# NCS_Wireless_Indicator_leds.net
KiCad netlist of a schematic drawn in Altium Designer
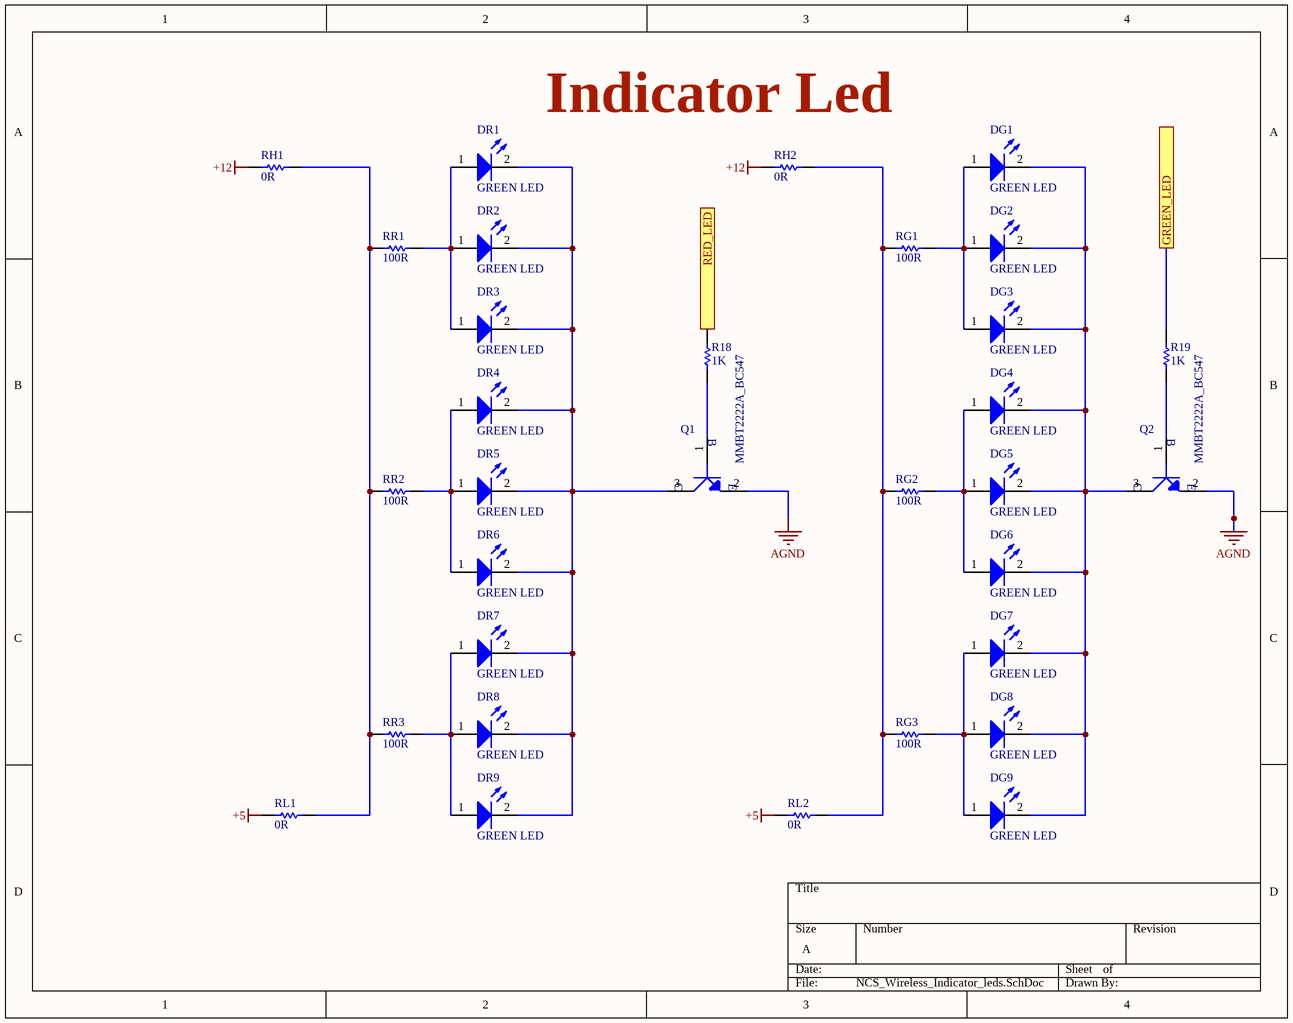
[diagram p0: NCS_Wireless_Indicator_leds.SchDoc]

(export (version "E")
  (design (tool "Eeschema 10.0.6"))
  (components
    (comp (ref "DG1")
      (value "GREEN LED")
      (footprint "LED_1208")
      (description "LED Uni-Color Red 2-Pin Chip 1208(3020Metric) T/R")
      (fields
        (field (name "MANUFACTURER") "QT-Brightek")
        (field (name "MANUFACTURER PART NUMBER") "QBLP653-R")
      )
      (libsource (lib "schlib") (part "QBLP653-R"))
    )
    (comp (ref "DG2")
      (value "GREEN LED")
      (footprint "LED_1208")
      (description "LED Uni-Color Red 2-Pin Chip 1208(3020Metric) T/R")
      (fields
        (field (name "MANUFACTURER") "QT-Brightek")
        (field (name "MANUFACTURER PART NUMBER") "QBLP653-R")
      )
      (libsource (lib "schlib") (part "QBLP653-R"))
    )
    (comp (ref "DG3")
      (value "GREEN LED")
      (footprint "LED_1208")
      (description "LED Uni-Color Red 2-Pin Chip 1208(3020Metric) T/R")
      (fields
        (field (name "MANUFACTURER") "QT-Brightek")
        (field (name "MANUFACTURER PART NUMBER") "QBLP653-R")
      )
      (libsource (lib "schlib") (part "QBLP653-R"))
    )
    (comp (ref "DG4")
      (value "GREEN LED")
      (footprint "LED_1208")
      (description "LED Uni-Color Red 2-Pin Chip 1208(3020Metric) T/R")
      (fields
        (field (name "MANUFACTURER") "QT-Brightek")
        (field (name "MANUFACTURER PART NUMBER") "QBLP653-R")
      )
      (libsource (lib "schlib") (part "QBLP653-R"))
    )
    (comp (ref "DG5")
      (value "GREEN LED")
      (footprint "LED_1208")
      (description "LED Uni-Color Red 2-Pin Chip 1208(3020Metric) T/R")
      (fields
        (field (name "MANUFACTURER") "QT-Brightek")
        (field (name "MANUFACTURER PART NUMBER") "QBLP653-R")
      )
      (libsource (lib "schlib") (part "QBLP653-R"))
    )
    (comp (ref "DG6")
      (value "GREEN LED")
      (footprint "LED_1208")
      (description "LED Uni-Color Red 2-Pin Chip 1208(3020Metric) T/R")
      (fields
        (field (name "MANUFACTURER") "QT-Brightek")
        (field (name "MANUFACTURER PART NUMBER") "QBLP653-R")
      )
      (libsource (lib "schlib") (part "QBLP653-R"))
    )
    (comp (ref "DG7")
      (value "GREEN LED")
      (footprint "LED_1208")
      (description "LED Uni-Color Red 2-Pin Chip 1208(3020Metric) T/R")
      (fields
        (field (name "MANUFACTURER") "QT-Brightek")
        (field (name "MANUFACTURER PART NUMBER") "QBLP653-R")
      )
      (libsource (lib "schlib") (part "QBLP653-R"))
    )
    (comp (ref "DG8")
      (value "GREEN LED")
      (footprint "LED_1208")
      (description "LED Uni-Color Red 2-Pin Chip 1208(3020Metric) T/R")
      (fields
        (field (name "MANUFACTURER") "QT-Brightek")
        (field (name "MANUFACTURER PART NUMBER") "QBLP653-R")
      )
      (libsource (lib "schlib") (part "QBLP653-R"))
    )
    (comp (ref "DG9")
      (value "GREEN LED")
      (footprint "LED_1208")
      (description "LED Uni-Color Red 2-Pin Chip 1208(3020Metric) T/R")
      (fields
        (field (name "MANUFACTURER") "QT-Brightek")
        (field (name "MANUFACTURER PART NUMBER") "QBLP653-R")
      )
      (libsource (lib "schlib") (part "QBLP653-R"))
    )
    (comp (ref "DR1")
      (value "GREEN LED")
      (footprint "LED_1208")
      (description "LED Uni-Color Red 2-Pin Chip 1208(3020Metric) T/R")
      (fields
        (field (name "MANUFACTURER") "QT-Brightek")
        (field (name "MANUFACTURER PART NUMBER") "QBLP653-R")
      )
      (libsource (lib "schlib") (part "QBLP653-R"))
    )
    (comp (ref "DR2")
      (value "GREEN LED")
      (footprint "LED_1208")
      (description "LED Uni-Color Red 2-Pin Chip 1208(3020Metric) T/R")
      (fields
        (field (name "MANUFACTURER") "QT-Brightek")
        (field (name "MANUFACTURER PART NUMBER") "QBLP653-R")
      )
      (libsource (lib "schlib") (part "QBLP653-R"))
    )
    (comp (ref "DR3")
      (value "GREEN LED")
      (footprint "LED_1208")
      (description "LED Uni-Color Red 2-Pin Chip 1208(3020Metric) T/R")
      (fields
        (field (name "MANUFACTURER") "QT-Brightek")
        (field (name "MANUFACTURER PART NUMBER") "QBLP653-R")
      )
      (libsource (lib "schlib") (part "QBLP653-R"))
    )
    (comp (ref "DR4")
      (value "GREEN LED")
      (footprint "LED_1208")
      (description "LED Uni-Color Red 2-Pin Chip 1208(3020Metric) T/R")
      (fields
        (field (name "MANUFACTURER") "QT-Brightek")
        (field (name "MANUFACTURER PART NUMBER") "QBLP653-R")
      )
      (libsource (lib "schlib") (part "QBLP653-R"))
    )
    (comp (ref "DR5")
      (value "GREEN LED")
      (footprint "LED_1208")
      (description "LED Uni-Color Red 2-Pin Chip 1208(3020Metric) T/R")
      (fields
        (field (name "MANUFACTURER") "QT-Brightek")
        (field (name "MANUFACTURER PART NUMBER") "QBLP653-R")
      )
      (libsource (lib "schlib") (part "QBLP653-R"))
    )
    (comp (ref "DR6")
      (value "GREEN LED")
      (footprint "LED_1208")
      (description "LED Uni-Color Red 2-Pin Chip 1208(3020Metric) T/R")
      (fields
        (field (name "MANUFACTURER") "QT-Brightek")
        (field (name "MANUFACTURER PART NUMBER") "QBLP653-R")
      )
      (libsource (lib "schlib") (part "QBLP653-R"))
    )
    (comp (ref "DR7")
      (value "GREEN LED")
      (footprint "LED_1208")
      (description "LED Uni-Color Red 2-Pin Chip 1208(3020Metric) T/R")
      (fields
        (field (name "MANUFACTURER") "QT-Brightek")
        (field (name "MANUFACTURER PART NUMBER") "QBLP653-R")
      )
      (libsource (lib "schlib") (part "QBLP653-R"))
    )
    (comp (ref "DR8")
      (value "GREEN LED")
      (footprint "LED_1208")
      (description "LED Uni-Color Red 2-Pin Chip 1208(3020Metric) T/R")
      (fields
        (field (name "MANUFACTURER") "QT-Brightek")
        (field (name "MANUFACTURER PART NUMBER") "QBLP653-R")
      )
      (libsource (lib "schlib") (part "QBLP653-R"))
    )
    (comp (ref "DR9")
      (value "GREEN LED")
      (footprint "LED_1208")
      (description "LED Uni-Color Red 2-Pin Chip 1208(3020Metric) T/R")
      (fields
        (field (name "MANUFACTURER") "QT-Brightek")
        (field (name "MANUFACTURER PART NUMBER") "QBLP653-R")
      )
      (libsource (lib "schlib") (part "QBLP653-R"))
    )
    (comp (ref "Q1")
      (value "MMBT2222A_BC547")
      (footprint "MMBT2222A_SOT23")
      (description "Trans GP BJT NPN 40V 0.6A 250mW Automotive 3-Pin SOT-23 T/R")
      (fields (field (name "MANUFACTURER") "Infineon") (field (name "MANUFACTURER PART NUMBER") "MMBT2222A"))
      (libsource (lib "BSCU_SMD_lib") (part "MMBT2222A"))
    )
    (comp (ref "Q2")
      (value "MMBT2222A_BC547")
      (footprint "MMBT2222A_SOT23")
      (description "Trans GP BJT NPN 40V 0.6A 250mW Automotive 3-Pin SOT-23 T/R")
      (fields (field (name "MANUFACTURER") "Infineon") (field (name "MANUFACTURER PART NUMBER") "MMBT2222A"))
      (libsource (lib "BSCU_SMD_lib") (part "MMBT2222A"))
    )
    (comp (ref "R18")
      (value "1K")
      (footprint "RC0805FR-7W330RL")
      (description "Res Thick Film 0805 330 Ohm 1% 0.25W(1/4W) ±200ppm/C Pad SMD T/R")
      (fields
        (field (name "MANUFACTURER") "Yageo")
        (field (name "MANUFACTURER PART NUMBER") "RC0805FR-7W330RL")
      )
      (libsource (lib "schlib") (part "RC0805FR-7W330RL"))
    )
    (comp (ref "R19")
      (value "1K")
      (footprint "RC0805FR-7W330RL")
      (description "Res Thick Film 0805 330 Ohm 1% 0.25W(1/4W) ±200ppm/C Pad SMD T/R")
      (fields
        (field (name "MANUFACTURER") "Yageo")
        (field (name "MANUFACTURER PART NUMBER") "RC0805FR-7W330RL")
      )
      (libsource (lib "schlib") (part "RC0805FR-7W330RL"))
    )
    (comp (ref "RG1")
      (value "100R")
      (footprint "RC0805FR-7W330RL")
      (description "Res Thick Film 0805 330 Ohm 1% 0.25W(1/4W) ±200ppm/C Pad SMD T/R")
      (fields
        (field (name "MANUFACTURER") "Yageo")
        (field (name "MANUFACTURER PART NUMBER") "RC0805FR-7W330RL")
      )
      (libsource (lib "schlib") (part "RC0805FR-7W330RL"))
    )
    (comp (ref "RG2")
      (value "100R")
      (footprint "RC0805FR-7W330RL")
      (description "Res Thick Film 0805 330 Ohm 1% 0.25W(1/4W) ±200ppm/C Pad SMD T/R")
      (fields
        (field (name "MANUFACTURER") "Yageo")
        (field (name "MANUFACTURER PART NUMBER") "RC0805FR-7W330RL")
      )
      (libsource (lib "schlib") (part "RC0805FR-7W330RL"))
    )
    (comp (ref "RG3")
      (value "100R")
      (footprint "RC0805FR-7W330RL")
      (description "Res Thick Film 0805 330 Ohm 1% 0.25W(1/4W) ±200ppm/C Pad SMD T/R")
      (fields
        (field (name "MANUFACTURER") "Yageo")
        (field (name "MANUFACTURER PART NUMBER") "RC0805FR-7W330RL")
      )
      (libsource (lib "schlib") (part "RC0805FR-7W330RL"))
    )
    (comp (ref "RH1")
      (value "0R")
      (footprint "RC0805FR-7W330RL")
      (description "Res Thick Film 0805 330 Ohm 1% 0.25W(1/4W) ±200ppm/C Pad SMD T/R")
      (fields
        (field (name "MANUFACTURER") "Yageo")
        (field (name "MANUFACTURER PART NUMBER") "RC0805FR-7W330RL")
      )
      (libsource (lib "schlib") (part "RC0805FR-7W330RL"))
    )
    (comp (ref "RH2")
      (value "0R")
      (footprint "RC0805FR-7W330RL")
      (description "Res Thick Film 0805 330 Ohm 1% 0.25W(1/4W) ±200ppm/C Pad SMD T/R")
      (fields
        (field (name "MANUFACTURER") "Yageo")
        (field (name "MANUFACTURER PART NUMBER") "RC0805FR-7W330RL")
      )
      (libsource (lib "schlib") (part "RC0805FR-7W330RL"))
    )
    (comp (ref "RL1")
      (value "0R")
      (footprint "RC0805FR-7W330RL")
      (description "Res Thick Film 0805 330 Ohm 1% 0.25W(1/4W) ±200ppm/C Pad SMD T/R")
      (fields
        (field (name "MANUFACTURER") "Yageo")
        (field (name "MANUFACTURER PART NUMBER") "RC0805FR-7W330RL")
      )
      (libsource (lib "schlib") (part "RC0805FR-7W330RL"))
    )
    (comp (ref "RL2")
      (value "0R")
      (footprint "RC0805FR-7W330RL")
      (description "Res Thick Film 0805 330 Ohm 1% 0.25W(1/4W) ±200ppm/C Pad SMD T/R")
      (fields
        (field (name "MANUFACTURER") "Yageo")
        (field (name "MANUFACTURER PART NUMBER") "RC0805FR-7W330RL")
      )
      (libsource (lib "schlib") (part "RC0805FR-7W330RL"))
    )
    (comp (ref "RR1")
      (value "100R")
      (footprint "RC0805FR-7W330RL")
      (description "Res Thick Film 0805 330 Ohm 1% 0.25W(1/4W) ±200ppm/C Pad SMD T/R")
      (fields
        (field (name "MANUFACTURER") "Yageo")
        (field (name "MANUFACTURER PART NUMBER") "RC0805FR-7W330RL")
      )
      (libsource (lib "schlib") (part "RC0805FR-7W330RL"))
    )
    (comp (ref "RR2")
      (value "100R")
      (footprint "RC0805FR-7W330RL")
      (description "Res Thick Film 0805 330 Ohm 1% 0.25W(1/4W) ±200ppm/C Pad SMD T/R")
      (fields
        (field (name "MANUFACTURER") "Yageo")
        (field (name "MANUFACTURER PART NUMBER") "RC0805FR-7W330RL")
      )
      (libsource (lib "schlib") (part "RC0805FR-7W330RL"))
    )
    (comp (ref "RR3")
      (value "100R")
      (footprint "RC0805FR-7W330RL")
      (description "Res Thick Film 0805 330 Ohm 1% 0.25W(1/4W) ±200ppm/C Pad SMD T/R")
      (fields
        (field (name "MANUFACTURER") "Yageo")
        (field (name "MANUFACTURER PART NUMBER") "RC0805FR-7W330RL")
      )
      (libsource (lib "schlib") (part "RC0805FR-7W330RL"))
    )
  )
  (nets
    (net (code "1") (name "+5") (class "Default")
      (node (ref "RL1") (pin "1") (pinfunction "1_1") (pintype "passive"))
      (node (ref "RL2") (pin "1") (pinfunction "1_1") (pintype "passive"))
    )
    (net (code "2") (name "+12") (class "Default")
      (node (ref "RH1") (pin "1") (pinfunction "1_1") (pintype "passive"))
      (node (ref "RH2") (pin "1") (pinfunction "1_1") (pintype "passive"))
    )
    (net (code "3") (name "/GREEN_LED") (class "Default")
      (node (ref "R19") (pin "2") (pinfunction "2_2") (pintype "passive"))
    )
    (net (code "4") (name "/RED_LED") (class "Default")
      (node (ref "R18") (pin "2") (pinfunction "2_2") (pintype "passive"))
    )
    (net (code "5") (name "AGND") (class "Default")
      (node (ref "Q1") (pin "2") (pinfunction "E_2") (pintype "passive"))
      (node (ref "Q2") (pin "2") (pinfunction "E_2") (pintype "passive"))
    )
    (net (code "6") (name "Net-(DG1-A)") (class "Default")
      (node (ref "DG1") (pin "1") (pinfunction "A_1") (pintype "passive"))
      (node (ref "DG2") (pin "1") (pinfunction "A_1") (pintype "passive"))
      (node (ref "DG3") (pin "1") (pinfunction "A_1") (pintype "passive"))
      (node (ref "RG1") (pin "2") (pinfunction "2_2") (pintype "passive"))
    )
    (net (code "7") (name "Net-(DG1-K)") (class "Default")
      (node (ref "DG1") (pin "2") (pinfunction "K_2") (pintype "passive"))
      (node (ref "DG2") (pin "2") (pinfunction "K_2") (pintype "passive"))
      (node (ref "DG3") (pin "2") (pinfunction "K_2") (pintype "passive"))
      (node (ref "DG4") (pin "2") (pinfunction "K_2") (pintype "passive"))
      (node (ref "DG5") (pin "2") (pinfunction "K_2") (pintype "passive"))
      (node (ref "DG6") (pin "2") (pinfunction "K_2") (pintype "passive"))
      (node (ref "DG7") (pin "2") (pinfunction "K_2") (pintype "passive"))
      (node (ref "DG8") (pin "2") (pinfunction "K_2") (pintype "passive"))
      (node (ref "DG9") (pin "2") (pinfunction "K_2") (pintype "passive"))
      (node (ref "Q2") (pin "3") (pinfunction "C_3") (pintype "passive"))
    )
    (net (code "8") (name "Net-(DG4-A)") (class "Default")
      (node (ref "DG4") (pin "1") (pinfunction "A_1") (pintype "passive"))
      (node (ref "DG5") (pin "1") (pinfunction "A_1") (pintype "passive"))
      (node (ref "DG6") (pin "1") (pinfunction "A_1") (pintype "passive"))
      (node (ref "RG2") (pin "2") (pinfunction "2_2") (pintype "passive"))
    )
    (net (code "9") (name "Net-(DG7-A)") (class "Default")
      (node (ref "DG7") (pin "1") (pinfunction "A_1") (pintype "passive"))
      (node (ref "DG8") (pin "1") (pinfunction "A_1") (pintype "passive"))
      (node (ref "DG9") (pin "1") (pinfunction "A_1") (pintype "passive"))
      (node (ref "RG3") (pin "2") (pinfunction "2_2") (pintype "passive"))
    )
    (net (code "10") (name "Net-(DR1-A)") (class "Default")
      (node (ref "DR1") (pin "1") (pinfunction "A_1") (pintype "passive"))
      (node (ref "DR2") (pin "1") (pinfunction "A_1") (pintype "passive"))
      (node (ref "DR3") (pin "1") (pinfunction "A_1") (pintype "passive"))
      (node (ref "RR1") (pin "2") (pinfunction "2_2") (pintype "passive"))
    )
    (net (code "11") (name "Net-(DR1-K)") (class "Default")
      (node (ref "DR1") (pin "2") (pinfunction "K_2") (pintype "passive"))
      (node (ref "DR2") (pin "2") (pinfunction "K_2") (pintype "passive"))
      (node (ref "DR3") (pin "2") (pinfunction "K_2") (pintype "passive"))
      (node (ref "DR4") (pin "2") (pinfunction "K_2") (pintype "passive"))
      (node (ref "DR5") (pin "2") (pinfunction "K_2") (pintype "passive"))
      (node (ref "DR6") (pin "2") (pinfunction "K_2") (pintype "passive"))
      (node (ref "DR7") (pin "2") (pinfunction "K_2") (pintype "passive"))
      (node (ref "DR8") (pin "2") (pinfunction "K_2") (pintype "passive"))
      (node (ref "DR9") (pin "2") (pinfunction "K_2") (pintype "passive"))
      (node (ref "Q1") (pin "3") (pinfunction "C_3") (pintype "passive"))
    )
    (net (code "12") (name "Net-(DR4-A)") (class "Default")
      (node (ref "DR4") (pin "1") (pinfunction "A_1") (pintype "passive"))
      (node (ref "DR5") (pin "1") (pinfunction "A_1") (pintype "passive"))
      (node (ref "DR6") (pin "1") (pinfunction "A_1") (pintype "passive"))
      (node (ref "RR2") (pin "2") (pinfunction "2_2") (pintype "passive"))
    )
    (net (code "13") (name "Net-(DR7-A)") (class "Default")
      (node (ref "DR7") (pin "1") (pinfunction "A_1") (pintype "passive"))
      (node (ref "DR8") (pin "1") (pinfunction "A_1") (pintype "passive"))
      (node (ref "DR9") (pin "1") (pinfunction "A_1") (pintype "passive"))
      (node (ref "RR3") (pin "2") (pinfunction "2_2") (pintype "passive"))
    )
    (net (code "14") (name "Net-(Q1-B)") (class "Default")
      (node (ref "Q1") (pin "1") (pinfunction "B_1") (pintype "passive"))
      (node (ref "R18") (pin "1") (pinfunction "1_1") (pintype "passive"))
    )
    (net (code "15") (name "Net-(Q2-B)") (class "Default")
      (node (ref "Q2") (pin "1") (pinfunction "B_1") (pintype "passive"))
      (node (ref "R19") (pin "1") (pinfunction "1_1") (pintype "passive"))
    )
    (net (code "16") (name "Net-(RG1-Pad1)") (class "Default")
      (node (ref "RG1") (pin "1") (pinfunction "1_1") (pintype "passive"))
      (node (ref "RG2") (pin "1") (pinfunction "1_1") (pintype "passive"))
      (node (ref "RG3") (pin "1") (pinfunction "1_1") (pintype "passive"))
      (node (ref "RH2") (pin "2") (pinfunction "2_2") (pintype "passive"))
      (node (ref "RL2") (pin "2") (pinfunction "2_2") (pintype "passive"))
    )
    (net (code "17") (name "Net-(RH1-Pad2)") (class "Default")
      (node (ref "RH1") (pin "2") (pinfunction "2_2") (pintype "passive"))
      (node (ref "RL1") (pin "2") (pinfunction "2_2") (pintype "passive"))
      (node (ref "RR1") (pin "1") (pinfunction "1_1") (pintype "passive"))
      (node (ref "RR2") (pin "1") (pinfunction "1_1") (pintype "passive"))
      (node (ref "RR3") (pin "1") (pinfunction "1_1") (pintype "passive"))
    )
  )
)
